# power.net
KiCad netlist of a schematic drawn in Altium Designer
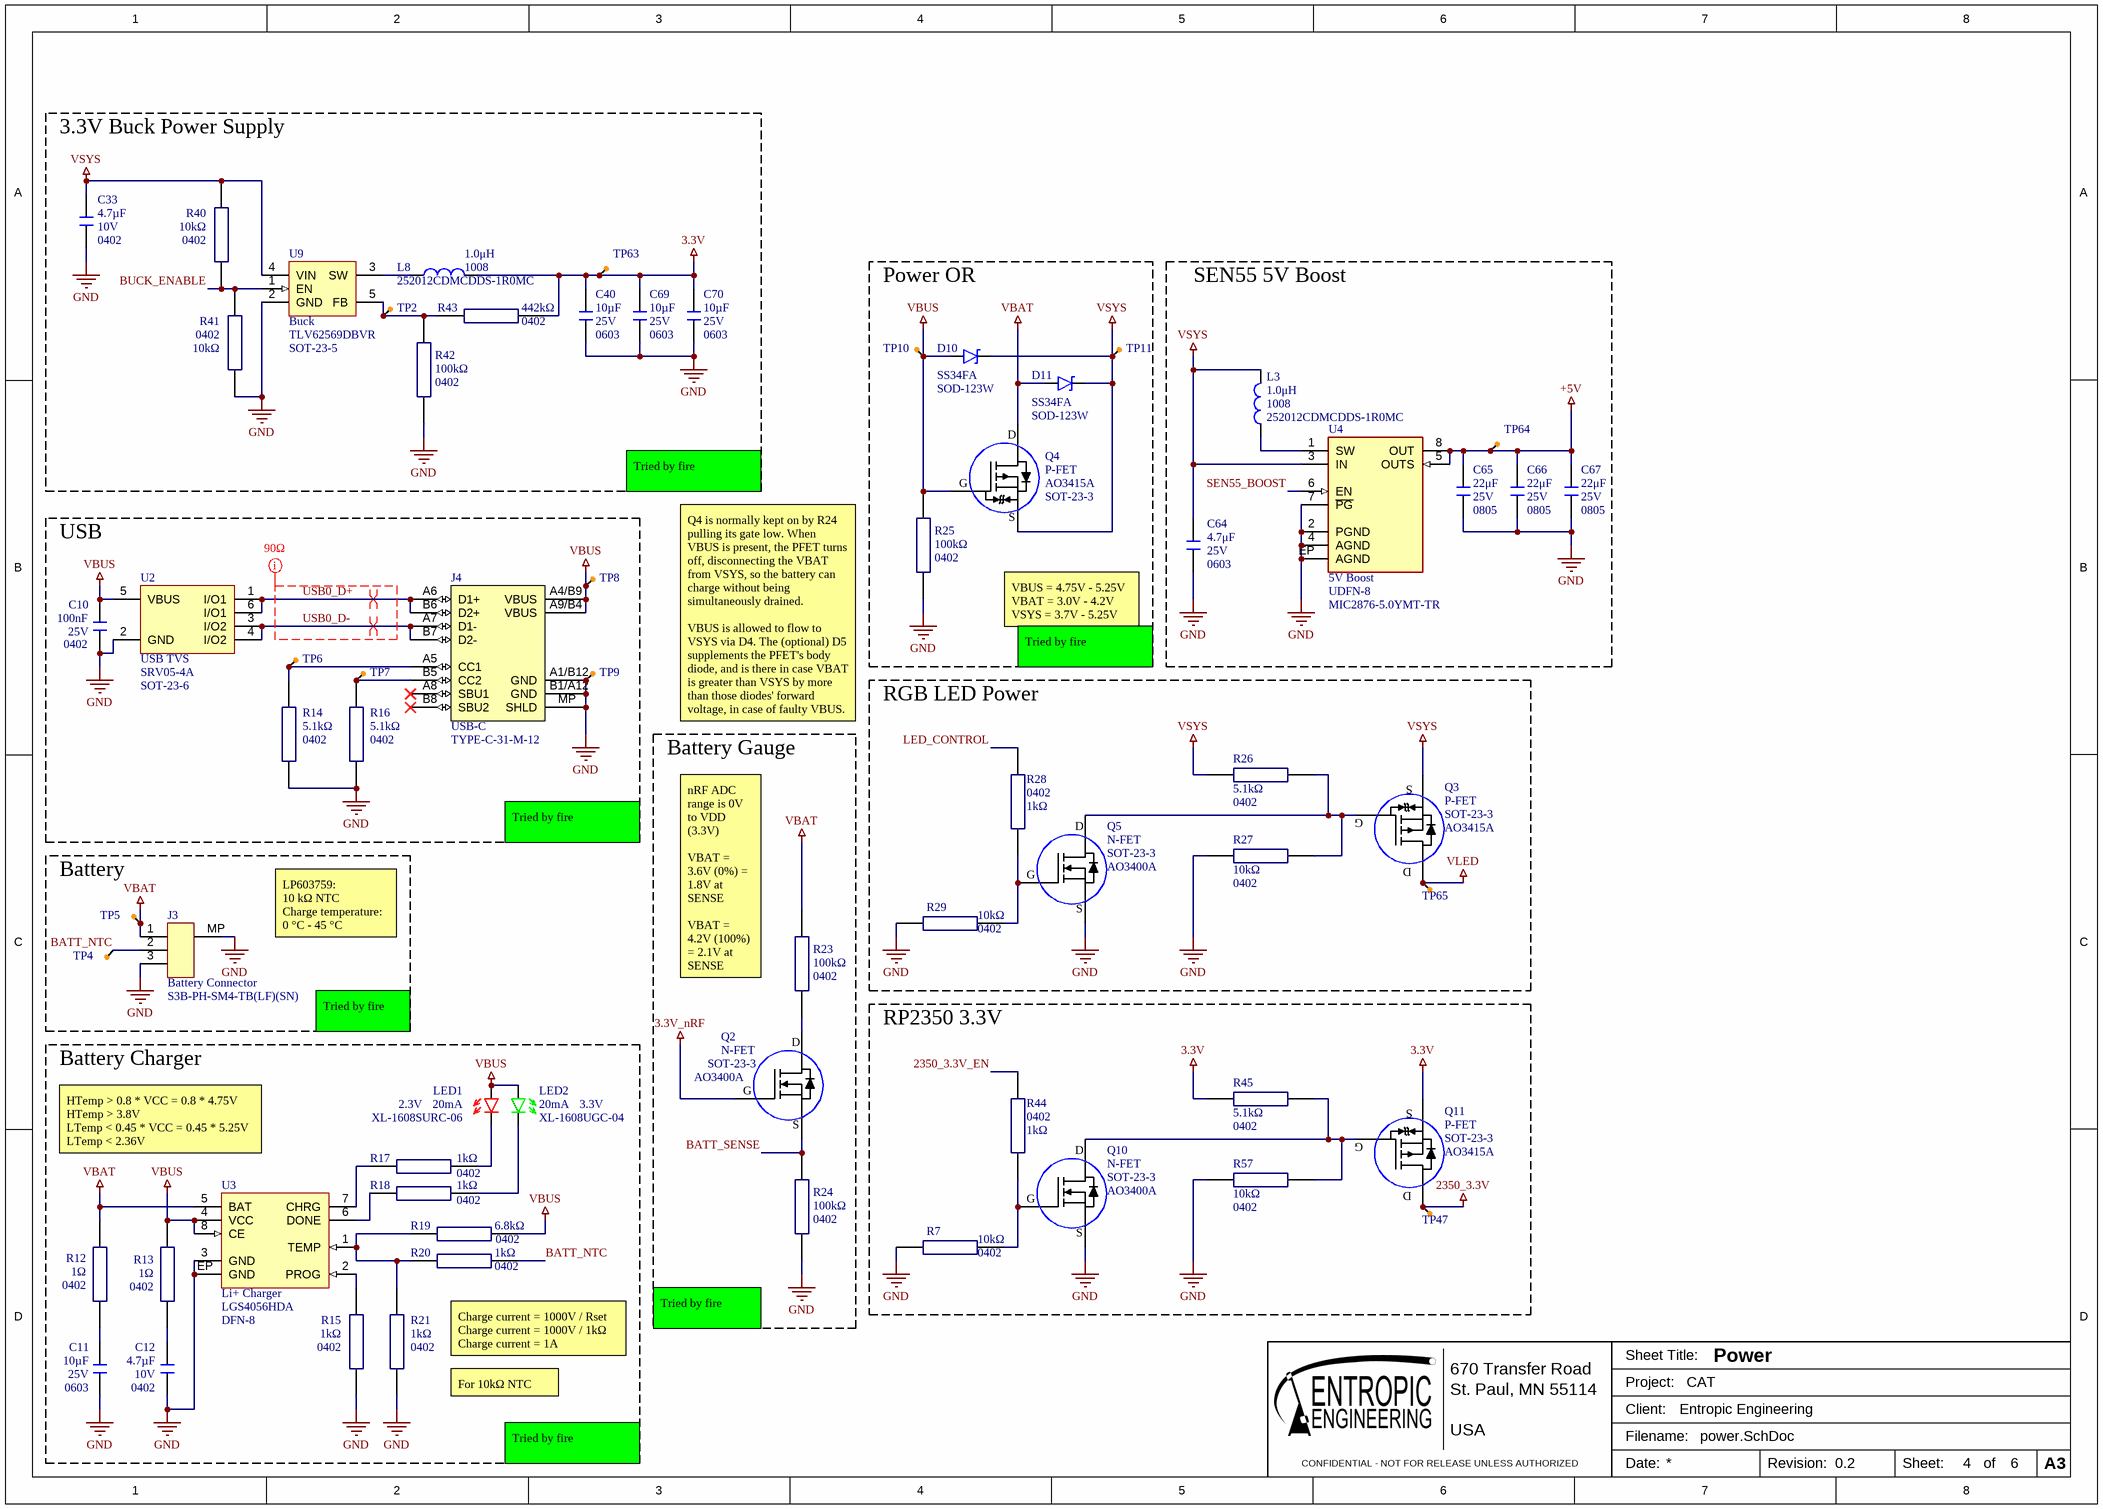
[diagram p0: power.SchDoc]

(export (version "E")
  (design (tool "Eeschema 10.0.6"))
  (components
    (comp (ref "C10")
      (value "GRM155R71E104KE14D")
      (footprint "0402_capacitor")
      (description "100 nF, 25 V, X7R, 0402 Chip capacitor")
      (fields
        (field (name "MANUFACTURER") "Murata")
        (field (name "TOLERANCE") "10%")
        (field (name "CASE CODE (IMPERIAL)") "0402")
        (field (name "VOLTAGE") "25V")
        (field (name "CAPACITANCE") "100nF")
      )
      (libsource (lib "cat") (part "GRM155R71E104KE14D"))
    )
    (comp (ref "C11")
      (value "10µF")
      (footprint "0603_capacitor")
      (description "10 µF, 25 V, X5R, 0603 Chip capacitor")
      (fields
        (field (name "MANUFACTURER") "Samsung")
        (field (name "CASE/PACKAGE") "0603")
        (field (name "TOLERANCE") "20%")
        (field (name "VOLTAGE RATING") "25V")
      )
      (libsource (lib "cat") (part "CL10A106MA8NRNC"))
    )
    (comp (ref "C12")
      (value "4.7µF")
      (footprint "0402_capacitor")
      (description "4.7 µF, 10 V, X5R, 0402 Chip capacitor")
      (fields
        (field (name "MANUFACTURER") "Samsung")
        (field (name "MANUFACTURER PART NUMBER") "CL05A475KP5NRNC")
        (field (name "VOLTAGE RATING") "10V")
        (field (name "CASE/PACKAGE") "0402")
      )
      (libsource (lib "cat") (part "CL05A475KP5NRNC"))
    )
    (comp (ref "C33")
      (value "4.7µF")
      (footprint "0402_capacitor")
      (description "4.7 µF, 10 V, X5R, 0402 Chip capacitor")
      (fields
        (field (name "MANUFACTURER") "Samsung")
        (field (name "MANUFACTURER PART NUMBER") "CL05A475KP5NRNC")
        (field (name "VOLTAGE RATING") "10V")
        (field (name "CASE/PACKAGE") "0402")
      )
      (libsource (lib "cat") (part "CL05A475KP5NRNC"))
    )
    (comp (ref "C40")
      (value "10µF")
      (footprint "0603_capacitor")
      (description "10 µF, 25 V, X5R, 0603 Chip capacitor")
      (fields
        (field (name "MANUFACTURER") "Samsung")
        (field (name "CASE/PACKAGE") "0603")
        (field (name "TOLERANCE") "20%")
        (field (name "VOLTAGE RATING") "25V")
      )
      (libsource (lib "cat") (part "CL10A106MA8NRNC"))
    )
    (comp (ref "C64")
      (value "4.7μF")
      (footprint "0603_capacitor")
      (description "4.7 μF, 25 V, X7R, 0603 Chip capacitor")
      (fields
        (field (name "MANUFACTURER") "TDK")
        (field (name "MANUFACTURER PART NUMBER") "C1608X5R1E475K080AC")
        (field (name "CASE/PACKAGE") "0603")
        (field (name "VOLTAGE RATING") "25V")
      )
      (libsource (lib "cat") (part "C1608X5R1E475K080AC"))
    )
    (comp (ref "C65")
      (value "22μF")
      (footprint "0805_capacitor")
      (description "22 μF, 25 V, X5R, 0805 Chip capacitor")
      (fields
        (field (name "MANUFACTURER") "Murata")
        (field (name "MANUFACTURER PART NUMBER") "GRT21BR61E226ME13L")
        (field (name "RATED DC VOLTAGE (URDC)") "25V")
        (field (name "CASE/PACKAGE") "0805")
      )
      (libsource (lib "cat") (part "GRT21BR61E226ME13L"))
    )
    (comp (ref "C66")
      (value "22μF")
      (footprint "0805_capacitor")
      (description "22 μF, 25 V, X5R, 0805 Chip capacitor")
      (fields
        (field (name "MANUFACTURER") "Murata")
        (field (name "MANUFACTURER PART NUMBER") "GRT21BR61E226ME13L")
        (field (name "RATED DC VOLTAGE (URDC)") "25V")
        (field (name "CASE/PACKAGE") "0805")
      )
      (libsource (lib "cat") (part "GRT21BR61E226ME13L"))
    )
    (comp (ref "C67")
      (value "22μF")
      (footprint "0805_capacitor")
      (description "22 μF, 25 V, X5R, 0805 Chip capacitor")
      (fields
        (field (name "MANUFACTURER") "Murata")
        (field (name "MANUFACTURER PART NUMBER") "GRT21BR61E226ME13L")
        (field (name "RATED DC VOLTAGE (URDC)") "25V")
        (field (name "CASE/PACKAGE") "0805")
      )
      (libsource (lib "cat") (part "GRT21BR61E226ME13L"))
    )
    (comp (ref "C69")
      (value "10µF")
      (footprint "0603_capacitor")
      (description "10 µF, 25 V, X5R, 0603 Chip capacitor")
      (fields
        (field (name "MANUFACTURER") "Samsung")
        (field (name "CASE/PACKAGE") "0603")
        (field (name "TOLERANCE") "20%")
        (field (name "VOLTAGE RATING") "25V")
      )
      (libsource (lib "cat") (part "CL10A106MA8NRNC"))
    )
    (comp (ref "C70")
      (value "10µF")
      (footprint "0603_capacitor")
      (description "10 µF, 25 V, X5R, 0603 Chip capacitor")
      (fields
        (field (name "MANUFACTURER") "Samsung")
        (field (name "CASE/PACKAGE") "0603")
        (field (name "TOLERANCE") "20%")
        (field (name "VOLTAGE RATING") "25V")
      )
      (libsource (lib "cat") (part "CL10A106MA8NRNC"))
    )
    (comp (ref "D10")
      (value "SS34FA")
      (footprint "SOD-123")
      (description "40 V, 3 A Schottky Rectifier, SOD-123FA")
      (fields
        (field (name "MANUFACTURER") "ON Semiconductor / Fairchild")
        (field (name "MANUFACTURER PART NUMBER") "SS34FA")
        (field (name "HOUSE_PART_NUMBER") "D-SCHOTTKY-3A-SOD123F-002")
        (field (name "CASE/PACKAGE") "SOD-123W")
      )
      (libsource (lib "cat") (part "SS34FA"))
    )
    (comp (ref "D11")
      (value "SS34FA")
      (footprint "SOD-123")
      (description "40 V, 3 A Schottky Rectifier, SOD-123FA")
      (fields
        (field (name "MANUFACTURER") "ON Semiconductor / Fairchild")
        (field (name "MANUFACTURER PART NUMBER") "SS34FA")
        (field (name "HOUSE_PART_NUMBER") "D-SCHOTTKY-3A-SOD123F-002")
        (field (name "CASE/PACKAGE") "SOD-123W")
      )
      (libsource (lib "cat") (part "SS34FA"))
    )
    (comp (ref "J3")
      (value "Battery Connector")
      (footprint "S3B-PH-SM4-TB")
      (description "3-Pin JST-PH connector, 2mm pitch, right-angle SMD")
      (fields
        (field (name "MANUFACTURER") "JST")
        (field (name "MANUFACTURER PART NUMBER") "S3B-PH-SM4-TB(LF)(SN)")
        (field (name "HOUSE_PART_NUMBER") "S3B-PH-SM4-TB(LF)(SN)")
      )
      (libsource (lib "cat") (part "S3B-PH-SM4-TB(LF)(SN)"))
    )
    (comp (ref "J4")
      (value "USB-C")
      (footprint "USB_C_2.0_M12")
      (description "USB-C 2.0 Female Connector")
      (fields
        (field (name "MANUFACTURER") "Global Connector Technology")
        (field (name "ALTERNATE PART NUMBER") "USB4105-GF-A")
        (field (name "MANUFACTURER PART NUMBER") "TYPE-C-31-M-12")
      )
      (libsource (lib "cat") (part "USB4105-GF-A"))
    )
    (comp (ref "L3")
      (value "1.0μH")
      (footprint "INDC2520X12N")
      (description "1 μH, 4.2 A, 1008 Inductor")
      (fields
        (field (name "MANUFACTURER") "Sumida")
        (field (name "HOUSE_PART_NUMBER") "L-1uH-1008-002")
        (field (name "PACKAGE") "1008")
        (field (name "MANUFACTURER PART NUMBER") "252012CDMCDDS-1R0MC")
      )
      (libsource (lib "") (part "252012CDMCDDS-1R0MC_1"))
    )
    (comp (ref "L8")
      (value "1.0μH")
      (footprint "INDC2520X12N")
      (description "1 μH, 4.2 A, 1008 Inductor")
      (fields
        (field (name "MANUFACTURER") "Sumida")
        (field (name "PACKAGE") "1008")
        (field (name "MANUFACTURER PART NUMBER") "252012CDMCDDS-1R0MC")
        (field (name "HOUSE_PART_NUMBER") "L-1uH-1008-002")
      )
      (libsource (lib "cat") (part "252012CDMCDDS-1R0MC"))
    )
    (comp (ref "LED1")
      (value "XL-1608SURC-06")
      (footprint "0603_DIODE")
      (description "Red LED, 1.9 - 2.3 V, 20 mA, 0603")
      (fields
        (field (name "MANUFACTURER") "XINGLIGHT")
        (field (name "CURRENT") "20mA")
        (field (name "FORWARD VOLTAGE") "2.3V")
        (field (name "MANUFACTURER PART NUMBER") "XL-1608SURC-06")
      )
      (libsource (lib "cat") (part "XL-1608SURC-06"))
    )
    (comp (ref "LED2")
      (value "XL-1608UGC-04")
      (footprint "0603_DIODE")
      (description "Green LED, 2.7 - 3.3 V, 20 mA, 0603")
      (fields
        (field (name "MANUFACTURER") "XINGLIGHT")
        (field (name "CURRENT") "20mA")
        (field (name "FORWARD VOLTAGE") "3.3V")
        (field (name "MANUFACTURER PART NUMBER") "XL-1608UGC-04")
      )
      (libsource (lib "cat") (part "XL-1608UGC-04"))
    )
    (comp (ref "Q2")
      (value "N-FET")
      (footprint "SOT95P280X115-3N")
      (description "N-FET, 30V, 5.7A, SOT-23-3")
      (fields
        (field (name "MANUFACTURER") "Alpha & Omega Semiconductor")
        (field (name "CASE/PACKAGE") "SOT-23-3")
        (field (name "MANUFACTURER PART NUMBER") "AO3400A")
        (field (name "HOUSE_PART_NUMBER") "AO3400A")
      )
      (libsource (lib "cat") (part "AO3400A"))
    )
    (comp (ref "Q3")
      (value "P-FET")
      (footprint "SOT95P280X115-3N")
      (description "P-FET, 30V, 6A, SOT-23-3")
      (fields
        (field (name "MANUFACTURER") "Alpha & Omega Semiconductor")
        (field (name "CASE/PACKAGE") "SOT-23-3")
        (field (name "MANUFACTURER PART NUMBER") "AO3415A")
        (field (name "HOUSE_PART_NUMBER") "AO3415A")
      )
      (libsource (lib "cat") (part "AO3415A"))
    )
    (comp (ref "Q4")
      (value "P-FET")
      (footprint "SOT95P280X115-3N")
      (description "P-FET, 30V, 6A, SOT-23-3")
      (fields
        (field (name "MANUFACTURER") "Alpha & Omega Semiconductor")
        (field (name "CASE/PACKAGE") "SOT-23-3")
        (field (name "MANUFACTURER PART NUMBER") "AO3415A")
        (field (name "HOUSE_PART_NUMBER") "AO3415A")
      )
      (libsource (lib "cat") (part "AO3415A"))
    )
    (comp (ref "Q5")
      (value "N-FET")
      (footprint "SOT95P280X115-3N")
      (description "N-FET, 30V, 5.7A, SOT-23-3")
      (fields
        (field (name "MANUFACTURER") "Alpha & Omega Semiconductor")
        (field (name "CASE/PACKAGE") "SOT-23-3")
        (field (name "MANUFACTURER PART NUMBER") "AO3400A")
        (field (name "HOUSE_PART_NUMBER") "AO3400A")
      )
      (libsource (lib "cat") (part "AO3400A"))
    )
    (comp (ref "Q10")
      (value "N-FET")
      (footprint "SOT95P280X115-3N")
      (description "N-FET, 30V, 5.7A, SOT-23-3")
      (fields
        (field (name "MANUFACTURER") "Alpha & Omega Semiconductor")
        (field (name "CASE/PACKAGE") "SOT-23-3")
        (field (name "MANUFACTURER PART NUMBER") "AO3400A")
        (field (name "HOUSE_PART_NUMBER") "AO3400A")
      )
      (libsource (lib "cat") (part "AO3400A"))
    )
    (comp (ref "Q11")
      (value "P-FET")
      (footprint "SOT95P280X115-3N")
      (description "P-FET, 30V, 6A, SOT-23-3")
      (fields
        (field (name "MANUFACTURER") "Alpha & Omega Semiconductor")
        (field (name "CASE/PACKAGE") "SOT-23-3")
        (field (name "MANUFACTURER PART NUMBER") "AO3415A")
        (field (name "HOUSE_PART_NUMBER") "AO3415A")
      )
      (libsource (lib "cat") (part "AO3415A"))
    )
    (comp (ref "R7")
      (value "10kΩ")
      (footprint "0402_resistor")
      (description "10 kΩ, 0402 Chip resistor")
      (fields
        (field (name "MANUFACTURER") "Yageo")
        (field (name "MANUFACTURER PART NUMBER") "RC0402FR-0710KL")
        (field (name "CASE CODE (IMPERIAL)") "0402")
      )
      (libsource (lib "cat") (part "RC0402FR-0710KL"))
    )
    (comp (ref "R12")
      (value "1Ω")
      (footprint "0402_resistor")
      (description "1 Ω, 0402 Chip resistor")
      (fields
        (field (name "MANUFACTURER") "Uniroyal")
        (field (name "MANUFACTURER PART NUMBER") "0402WGF100KTCE")
        (field (name "CASE/PACKAGE") "0402")
      )
      (libsource (lib "cat") (part "0402WGF100KTCE"))
    )
    (comp (ref "R13")
      (value "1Ω")
      (footprint "0402_resistor")
      (description "1 Ω, 0402 Chip resistor")
      (fields
        (field (name "MANUFACTURER") "Uniroyal")
        (field (name "MANUFACTURER PART NUMBER") "0402WGF100KTCE")
        (field (name "CASE/PACKAGE") "0402")
      )
      (libsource (lib "cat") (part "0402WGF100KTCE"))
    )
    (comp (ref "R14")
      (value "5.1kΩ")
      (footprint "0402_resistor")
      (description "5.1 kΩ, 0402 Chip resistor")
      (fields
        (field (name "MANUFACTURER") "Yageo")
        (field (name "MANUFACTURER PART NUMBER") "RC0402FR-075K1L")
        (field (name "CASE/PACKAGE") "0402")
      )
      (libsource (lib "cat") (part "RC0402FR-075K1L"))
    )
    (comp (ref "R15")
      (value "1kΩ")
      (footprint "0402_resistor")
      (description "1 kΩ, 0402 Chip resistor")
      (fields
        (field (name "MANUFACTURER") "Yageo")
        (field (name "MANUFACTURER PART NUMBER") "RC0402JR-071KL")
        (field (name "CASE/PACKAGE") "0402")
      )
      (libsource (lib "cat") (part "RC0402JR-071KL"))
    )
    (comp (ref "R16")
      (value "5.1kΩ")
      (footprint "0402_resistor")
      (description "5.1 kΩ, 0402 Chip resistor")
      (fields
        (field (name "MANUFACTURER") "Yageo")
        (field (name "MANUFACTURER PART NUMBER") "RC0402FR-075K1L")
        (field (name "CASE/PACKAGE") "0402")
      )
      (libsource (lib "cat") (part "RC0402FR-075K1L"))
    )
    (comp (ref "R17")
      (value "1kΩ")
      (footprint "0402_resistor")
      (description "1 kΩ, 0402 Chip resistor")
      (fields
        (field (name "MANUFACTURER") "Yageo")
        (field (name "MANUFACTURER PART NUMBER") "RC0402JR-071KL")
        (field (name "CASE/PACKAGE") "0402")
      )
      (libsource (lib "cat") (part "RC0402JR-071KL"))
    )
    (comp (ref "R18")
      (value "1kΩ")
      (footprint "0402_resistor")
      (description "1 kΩ, 0402 Chip resistor")
      (fields
        (field (name "MANUFACTURER") "Yageo")
        (field (name "MANUFACTURER PART NUMBER") "RC0402JR-071KL")
        (field (name "CASE/PACKAGE") "0402")
      )
      (libsource (lib "cat") (part "RC0402JR-071KL"))
    )
    (comp (ref "R19")
      (value "6.8kΩ")
      (footprint "0402_resistor")
      (description "6.8 kΩ, 0402 Chip resistor")
      (fields
        (field (name "MANUFACTURER") "Yageo")
        (field (name "MANUFACTURER PART NUMBER") "RC0402FR-076K8L")
        (field (name "CASE/PACKAGE") "0402")
      )
      (libsource (lib "cat") (part "RC0402FR-076K8L"))
    )
    (comp (ref "R20")
      (value "1kΩ")
      (footprint "0402_resistor")
      (description "1 kΩ, 0402 Chip resistor")
      (fields
        (field (name "MANUFACTURER") "Yageo")
        (field (name "MANUFACTURER PART NUMBER") "RC0402JR-071KL")
        (field (name "CASE/PACKAGE") "0402")
      )
      (libsource (lib "cat") (part "RC0402JR-071KL"))
    )
    (comp (ref "R21")
      (value "1kΩ")
      (footprint "0402_resistor")
      (description "1 kΩ, 0402 Chip resistor")
      (fields
        (field (name "MANUFACTURER") "Yageo")
        (field (name "MANUFACTURER PART NUMBER") "RC0402JR-071KL")
        (field (name "CASE/PACKAGE") "0402")
      )
      (libsource (lib "cat") (part "RC0402JR-071KL"))
    )
    (comp (ref "R23")
      (value "100kΩ")
      (footprint "0402_resistor")
      (description "100 kΩ, 0402 Chip resistor")
      (fields
        (field (name "MANUFACTURER") "Yageo")
        (field (name "MANUFACTURER PART NUMBER") "RC0402FR-07100KL")
        (field (name "CASE/PACKAGE") "0402")
      )
      (libsource (lib "cat") (part "RC0402FR-07100KL"))
    )
    (comp (ref "R24")
      (value "100kΩ")
      (footprint "0402_resistor")
      (description "100 kΩ, 0402 Chip resistor")
      (fields
        (field (name "MANUFACTURER") "Yageo")
        (field (name "MANUFACTURER PART NUMBER") "RC0402FR-07100KL")
        (field (name "CASE/PACKAGE") "0402")
      )
      (libsource (lib "cat") (part "RC0402FR-07100KL"))
    )
    (comp (ref "R25")
      (value "100kΩ")
      (footprint "0402_resistor")
      (description "100 kΩ, 0402 Chip resistor")
      (fields
        (field (name "MANUFACTURER") "Yageo")
        (field (name "MANUFACTURER PART NUMBER") "RC0402FR-07100KL")
        (field (name "CASE/PACKAGE") "0402")
      )
      (libsource (lib "cat") (part "RC0402FR-07100KL"))
    )
    (comp (ref "R26")
      (value "5.1kΩ")
      (footprint "0402_resistor")
      (description "5.1 kΩ, 0402 Chip resistor")
      (fields
        (field (name "MANUFACTURER") "Yageo")
        (field (name "MANUFACTURER PART NUMBER") "RC0402FR-075K1L")
        (field (name "CASE/PACKAGE") "0402")
      )
      (libsource (lib "cat") (part "RC0402FR-075K1L"))
    )
    (comp (ref "R27")
      (value "10kΩ")
      (footprint "0402_resistor")
      (description "10 kΩ, 0402 Chip resistor")
      (fields
        (field (name "MANUFACTURER") "Yageo")
        (field (name "MANUFACTURER PART NUMBER") "RC0402FR-0710KL")
        (field (name "CASE CODE (IMPERIAL)") "0402")
      )
      (libsource (lib "cat") (part "RC0402FR-0710KL"))
    )
    (comp (ref "R28")
      (value "1kΩ")
      (footprint "0402_resistor")
      (description "1 kΩ, 0402 Chip resistor")
      (fields
        (field (name "MANUFACTURER") "Yageo")
        (field (name "MANUFACTURER PART NUMBER") "RC0402JR-071KL")
        (field (name "CASE/PACKAGE") "0402")
      )
      (libsource (lib "cat") (part "RC0402JR-071KL"))
    )
    (comp (ref "R29")
      (value "10kΩ")
      (footprint "0402_resistor")
      (description "10 kΩ, 0402 Chip resistor")
      (fields
        (field (name "MANUFACTURER") "Yageo")
        (field (name "MANUFACTURER PART NUMBER") "RC0402FR-0710KL")
        (field (name "CASE CODE (IMPERIAL)") "0402")
      )
      (libsource (lib "cat") (part "RC0402FR-0710KL"))
    )
    (comp (ref "R40")
      (value "10kΩ")
      (footprint "0402_resistor")
      (description "10 kΩ, 0402 Chip resistor")
      (fields
        (field (name "MANUFACTURER") "Yageo")
        (field (name "MANUFACTURER PART NUMBER") "RC0402FR-0710KL")
        (field (name "CASE CODE (IMPERIAL)") "0402")
      )
      (libsource (lib "cat") (part "RC0402FR-0710KL"))
    )
    (comp (ref "R41")
      (value "10kΩ")
      (footprint "0402_resistor")
      (description "10 kΩ, 0402 Chip resistor")
      (fields
        (field (name "MANUFACTURER") "Yageo")
        (field (name "MANUFACTURER PART NUMBER") "RC0402FR-0710KL")
        (field (name "CASE CODE (IMPERIAL)") "0402")
      )
      (libsource (lib "cat") (part "RC0402FR-0710KL"))
    )
    (comp (ref "R42")
      (value "100kΩ")
      (footprint "0402_resistor")
      (description "100 kΩ, 0402 Chip resistor")
      (fields
        (field (name "MANUFACTURER") "Yageo")
        (field (name "MANUFACTURER PART NUMBER") "RC0402FR-07100KL")
        (field (name "CASE/PACKAGE") "0402")
      )
      (libsource (lib "cat") (part "RC0402FR-07100KL"))
    )
    (comp (ref "R43")
      (value "442kΩ")
      (footprint "0402_resistor")
      (description "442 kΩ, 0402 Chip resistor")
      (fields
        (field (name "MANUFACTURER") "Yageo")
        (field (name "MANUFACTURER PART NUMBER") "RC0402FR-07442KL")
        (field (name "CASE/PACKAGE") "0402")
      )
      (libsource (lib "cat") (part "RC0402FR-07442KL"))
    )
    (comp (ref "R44")
      (value "1kΩ")
      (footprint "0402_resistor")
      (description "1 kΩ, 0402 Chip resistor")
      (fields
        (field (name "MANUFACTURER") "Yageo")
        (field (name "MANUFACTURER PART NUMBER") "RC0402JR-071KL")
        (field (name "CASE/PACKAGE") "0402")
      )
      (libsource (lib "cat") (part "RC0402JR-071KL"))
    )
    (comp (ref "R45")
      (value "5.1kΩ")
      (footprint "0402_resistor")
      (description "5.1 kΩ, 0402 Chip resistor")
      (fields
        (field (name "MANUFACTURER") "Yageo")
        (field (name "MANUFACTURER PART NUMBER") "RC0402FR-075K1L")
        (field (name "CASE/PACKAGE") "0402")
      )
      (libsource (lib "cat") (part "RC0402FR-075K1L"))
    )
    (comp (ref "R57")
      (value "10kΩ")
      (footprint "0402_resistor")
      (description "10 kΩ, 0402 Chip resistor")
      (fields
        (field (name "MANUFACTURER") "Yageo")
        (field (name "MANUFACTURER PART NUMBER") "RC0402FR-0710KL")
        (field (name "CASE CODE (IMPERIAL)") "0402")
      )
      (libsource (lib "cat") (part "RC0402FR-0710KL"))
    )
    (comp (ref "TP2")
      (value "test_point-1")
      (footprint "test_point-1")
      (description "Test point")
      (libsource (lib "cat") (part "test_point-1"))
    )
    (comp (ref "TP4")
      (value "test_point-1")
      (footprint "test_point-1")
      (description "Test point")
      (libsource (lib "cat") (part "test_point-1"))
    )
    (comp (ref "TP5")
      (value "VBAT")
      (footprint "test_point-1")
      (description "Test point")
      (libsource (lib "cat") (part "test_point-1"))
    )
    (comp (ref "TP6")
      (value "test_point-1")
      (footprint "test_point-1")
      (description "Test point")
      (libsource (lib "cat") (part "test_point-1"))
    )
    (comp (ref "TP7")
      (value "test_point-1")
      (footprint "test_point-1")
      (description "Test point")
      (libsource (lib "cat") (part "test_point-1"))
    )
    (comp (ref "TP8")
      (value "VBUS")
      (footprint "test_point-1")
      (description "Test point")
      (libsource (lib "cat") (part "test_point-1"))
    )
    (comp (ref "TP9")
      (value "GND")
      (footprint "test_point-1")
      (description "Test point")
      (libsource (lib "cat") (part "test_point-1"))
    )
    (comp (ref "TP10")
      (value "VBUS")
      (footprint "test_point-1")
      (description "Test point")
      (libsource (lib "cat") (part "test_point-1"))
    )
    (comp (ref "TP11")
      (value "VSYS")
      (footprint "test_point-1")
      (description "Test point")
      (libsource (lib "cat") (part "test_point-1"))
    )
    (comp (ref "TP47")
      (value "VLED")
      (footprint "test_point-1")
      (description "Test point")
      (libsource (lib "cat") (part "test_point-1"))
    )
    (comp (ref "TP63")
      (value "Main 3.3V")
      (footprint "test_point-1")
      (description "Test point")
      (libsource (lib "cat") (part "test_point-1"))
    )
    (comp (ref "TP64")
      (value "Sensors 5V")
      (footprint "test_point-1")
      (description "Test point")
      (libsource (lib "cat") (part "test_point-1"))
    )
    (comp (ref "TP65")
      (value "VLED")
      (footprint "test_point-1")
      (description "Test point")
      (libsource (lib "cat") (part "test_point-1"))
    )
    (comp (ref "U2")
      (value "USB TVS")
      (footprint "SOT95P280X110-6N")
      (description "TVS DIODE ARRAY SOT23-6")
      (fields
        (field (name "MANUFACTURER") "SMC Diodes")
        (field (name "CASE/PACKAGE") "SOT-23-6")
        (field (name "MANUFACTURER PART NUMBER") "SRV05-4A")
        (field (name "HOUSE_PART_NUMBER") "SRV05-4A")
      )
      (libsource (lib "cat") (part "SRV05-4A"))
    )
    (comp (ref "U3")
      (value "Li+ Charger")
      (footprint "SON50P200X80_HS-9N")
      (description "Battery Charger, DFN-8(2x2)")
      (fields
        (field (name "MANUFACTURER PART NUMBER") "LGS4056HDA")
        (field (name "PACKAGE") "DFN-8")
        (field (name "HOUSE_PART_NUMBER") "LGS4056HDA")
      )
      (libsource (lib "cat") (part "LGS4056H"))
    )
    (comp (ref "U4")
      (value "5V Boost")
      (footprint "SON50P200X50_HS-9N")
      (description "5V Synchronous Boost, UDFN-8")
      (fields
        (field (name "MANUFACTURER") "Microchip")
        (field (name "CASE/PACKAGE") "UDFN-8")
        (field (name "MANUFACTURER PART NUMBER") "MIC2876-5.0YMT-TR")
      )
      (libsource (lib "cat") (part "MIC2876-5.0YMT-TR"))
    )
    (comp (ref "U9")
      (value "Buck")
      (footprint "SOT95P280X115-5N")
      (description "Buck converter, 2.5-5.5 Vin, 0.6 - 5.5 Vout, 2A, SOT-23-5")
      (fields
        (field (name "MANUFACTURER") "Texas Instruments")
        (field (name "MANUFACTURER PART NUMBER") "TLV62569DBVR")
        (field (name "CASE/PACKAGE") "SOT-23-5")
        (field (name "HOUSE_PART_NUMBER") "TLV62569DBVR")
      )
      (libsource (lib "cat") (part "TLV62569DBVR"))
    )
  )
  (nets
    (net (code "1") (name "+5V") (class "Default")
      (node (ref "C65") (pin "2") (pinfunction "2_2") (pintype "passive"))
      (node (ref "C66") (pin "2") (pinfunction "2_2") (pintype "passive"))
      (node (ref "C67") (pin "2") (pinfunction "2_2") (pintype "passive"))
      (node (ref "TP64") (pin "1") (pinfunction "1_1") (pintype "passive"))
      (node (ref "U4") (pin "5") (pinfunction "OUTS_5") (pintype "input"))
      (node (ref "U4") (pin "8") (pinfunction "OUT_8") (pintype "power_in"))
    )
    (net (code "2") (name "/2350_3.3V_EN") (class "Default")
      (node (ref "R44") (pin "1") (pinfunction "1_1") (pintype "passive"))
    )
    (net (code "3") (name "/BATT_NTC") (class "Default")
      (node (ref "J3") (pin "2") (pintype "passive"))
      (node (ref "R20") (pin "1") (pinfunction "1_1") (pintype "passive"))
      (node (ref "TP4") (pin "1") (pinfunction "1_1") (pintype "passive"))
    )
    (net (code "4") (name "/BATT_SENSE") (class "Default")
      (node (ref "Q2") (pin "2") (pinfunction "S_2") (pintype "passive"))
      (node (ref "R24") (pin "2") (pinfunction "2_2") (pintype "passive"))
    )
    (net (code "5") (name "/BUCK_ENABLE") (class "Default")
      (node (ref "R40") (pin "1") (pinfunction "1_1") (pintype "passive"))
      (node (ref "R41") (pin "2") (pinfunction "2_2") (pintype "passive"))
      (node (ref "U9") (pin "1") (pinfunction "EN_1") (pintype "input"))
    )
    (net (code "6") (name "/LED_CONTROL") (class "Default")
      (node (ref "R28") (pin "1") (pinfunction "1_1") (pintype "passive"))
    )
    (net (code "7") (name "/SEN55_BOOST") (class "Default")
      (node (ref "U4") (pin "6") (pinfunction "EN_6") (pintype "input"))
    )
    (net (code "8") (name "/USB0_D+") (class "Default")
      (node (ref "J4") (pin "A6") (pinfunction "D1+_A6") (pintype "bidirectional"))
      (node (ref "J4") (pin "B6") (pinfunction "D2+_B6") (pintype "bidirectional"))
      (node (ref "U2") (pin "1") (pinfunction "I/O1_1") (pintype "passive"))
      (node (ref "U2") (pin "6") (pinfunction "I/O1_6") (pintype "passive"))
    )
    (net (code "9") (name "/USB0_D-") (class "Default")
      (node (ref "J4") (pin "A7") (pinfunction "D1-_A7") (pintype "bidirectional"))
      (node (ref "J4") (pin "B7") (pinfunction "D2-_B7") (pintype "bidirectional"))
      (node (ref "U2") (pin "3") (pinfunction "I/O2_3") (pintype "passive"))
      (node (ref "U2") (pin "4") (pinfunction "I/O2_4") (pintype "passive"))
    )
    (net (code "10") (name "3.3V") (class "Default")
      (node (ref "C40") (pin "2") (pinfunction "2_2") (pintype "passive"))
      (node (ref "C69") (pin "2") (pinfunction "2_2") (pintype "passive"))
      (node (ref "C70") (pin "2") (pinfunction "2_2") (pintype "passive"))
      (node (ref "L8") (pin "2") (pinfunction "2_2") (pintype "passive"))
      (node (ref "Q11") (pin "2") (pinfunction "S_2") (pintype "power_in"))
      (node (ref "R43") (pin "2") (pinfunction "2_2") (pintype "passive"))
      (node (ref "R45") (pin "2") (pinfunction "2_2") (pintype "passive"))
      (node (ref "TP63") (pin "1") (pinfunction "1_1") (pintype "passive"))
    )
    (net (code "11") (name "3.3V_nRF") (class "Default")
      (node (ref "Q2") (pin "1") (pinfunction "G_1") (pintype "passive"))
    )
    (net (code "12") (name "2350_3.3V") (class "Default")
      (node (ref "Q11") (pin "3") (pinfunction "D_3") (pintype "power_in"))
      (node (ref "TP47") (pin "1") (pinfunction "1_1") (pintype "passive"))
    )
    (net (code "13") (name "GND") (class "Default")
      (node (ref "C10") (pin "1") (pinfunction "1_1") (pintype "passive"))
      (node (ref "C11") (pin "1") (pinfunction "1_1") (pintype "passive"))
      (node (ref "C12") (pin "1") (pinfunction "1_1") (pintype "passive"))
      (node (ref "C33") (pin "1") (pinfunction "1_1") (pintype "passive"))
      (node (ref "C40") (pin "1") (pinfunction "1_1") (pintype "passive"))
      (node (ref "C64") (pin "1") (pinfunction "1_1") (pintype "passive"))
      (node (ref "C65") (pin "1") (pinfunction "1_1") (pintype "passive"))
      (node (ref "C66") (pin "1") (pinfunction "1_1") (pintype "passive"))
      (node (ref "C67") (pin "1") (pinfunction "1_1") (pintype "passive"))
      (node (ref "C69") (pin "1") (pinfunction "1_1") (pintype "passive"))
      (node (ref "C70") (pin "1") (pinfunction "1_1") (pintype "passive"))
      (node (ref "J3") (pin "3") (pintype "passive"))
      (node (ref "J3") (pin "MP") (pintype "passive"))
      (node (ref "J4") (pin "A1/B12") (pinfunction "GND_A1/B12") (pintype "power_in"))
      (node (ref "J4") (pin "B1/A12") (pinfunction "GND_B1/A12") (pintype "power_in"))
      (node (ref "J4") (pin "MP") (pinfunction "SHLD_MP") (pintype "passive"))
      (node (ref "Q10") (pin "2") (pinfunction "S_2") (pintype "passive"))
      (node (ref "Q5") (pin "2") (pinfunction "S_2") (pintype "passive"))
      (node (ref "R14") (pin "1") (pinfunction "1_1") (pintype "passive"))
      (node (ref "R15") (pin "1") (pinfunction "1_1") (pintype "passive"))
      (node (ref "R16") (pin "1") (pinfunction "1_1") (pintype "passive"))
      (node (ref "R21") (pin "1") (pinfunction "1_1") (pintype "passive"))
      (node (ref "R24") (pin "1") (pinfunction "1_1") (pintype "passive"))
      (node (ref "R25") (pin "1") (pinfunction "1_1") (pintype "passive"))
      (node (ref "R27") (pin "2") (pinfunction "2_2") (pintype "passive"))
      (node (ref "R29") (pin "2") (pinfunction "2_2") (pintype "passive"))
      (node (ref "R41") (pin "1") (pinfunction "1_1") (pintype "passive"))
      (node (ref "R42") (pin "1") (pinfunction "1_1") (pintype "passive"))
      (node (ref "R57") (pin "2") (pinfunction "2_2") (pintype "passive"))
      (node (ref "R7") (pin "2") (pinfunction "2_2") (pintype "passive"))
      (node (ref "TP9") (pin "1") (pinfunction "1_1") (pintype "passive"))
      (node (ref "U2") (pin "2") (pinfunction "GND_2") (pintype "passive"))
      (node (ref "U3") (pin "3") (pinfunction "GND_3") (pintype "power_in"))
      (node (ref "U3") (pin "EP") (pinfunction "GND_EP") (pintype "power_in"))
      (node (ref "U4") (pin "2") (pinfunction "PGND_2") (pintype "power_in"))
      (node (ref "U4") (pin "4") (pinfunction "AGND_4") (pintype "power_in"))
      (node (ref "U4") (pin "7") (pinfunction "~{PG}_7") (pintype "open_collector"))
      (node (ref "U4") (pin "EP") (pinfunction "AGND_EP") (pintype "power_in"))
      (node (ref "U9") (pin "2") (pinfunction "GND_2") (pintype "power_in"))
    )
    (net (code "14") (name "Net-(C11-Pad2)") (class "Default")
      (node (ref "C11") (pin "2") (pinfunction "2_2") (pintype "passive"))
      (node (ref "R12") (pin "1") (pinfunction "1_1") (pintype "passive"))
    )
    (net (code "15") (name "Net-(C12-Pad2)") (class "Default")
      (node (ref "C12") (pin "2") (pinfunction "2_2") (pintype "passive"))
      (node (ref "R13") (pin "1") (pinfunction "1_1") (pintype "passive"))
    )
    (net (code "16") (name "Net-(J4-CC1)") (class "Default")
      (node (ref "J4") (pin "A5") (pinfunction "CC1_A5") (pintype "bidirectional"))
      (node (ref "R14") (pin "2") (pinfunction "2_2") (pintype "passive"))
      (node (ref "TP6") (pin "1") (pinfunction "1_1") (pintype "passive"))
    )
    (net (code "17") (name "Net-(J4-CC2)") (class "Default")
      (node (ref "J4") (pin "B5") (pinfunction "CC2_B5") (pintype "bidirectional"))
      (node (ref "R16") (pin "2") (pinfunction "2_2") (pintype "passive"))
      (node (ref "TP7") (pin "1") (pinfunction "1_1") (pintype "passive"))
    )
    (net (code "18") (name "Net-(LED1-Pad1)") (class "Default")
      (node (ref "LED1") (pin "1") (pinfunction "1_1") (pintype "passive"))
      (node (ref "R17") (pin "1") (pinfunction "1_1") (pintype "passive"))
    )
    (net (code "19") (name "Net-(LED2-Pad1)") (class "Default")
      (node (ref "LED2") (pin "1") (pinfunction "1_1") (pintype "passive"))
      (node (ref "R18") (pin "1") (pinfunction "1_1") (pintype "passive"))
    )
    (net (code "20") (name "Net-(Q2-D)") (class "Default")
      (node (ref "Q2") (pin "3") (pinfunction "D_3") (pintype "passive"))
      (node (ref "R23") (pin "1") (pinfunction "1_1") (pintype "passive"))
    )
    (net (code "21") (name "Net-(Q3-G)") (class "Default")
      (node (ref "Q3") (pin "1") (pinfunction "G_1") (pintype "power_in"))
      (node (ref "Q5") (pin "3") (pinfunction "D_3") (pintype "passive"))
      (node (ref "R26") (pin "1") (pinfunction "1_1") (pintype "passive"))
      (node (ref "R27") (pin "1") (pinfunction "1_1") (pintype "passive"))
    )
    (net (code "22") (name "Net-(Q5-G)") (class "Default")
      (node (ref "Q5") (pin "1") (pinfunction "G_1") (pintype "passive"))
      (node (ref "R28") (pin "2") (pinfunction "2_2") (pintype "passive"))
      (node (ref "R29") (pin "1") (pinfunction "1_1") (pintype "passive"))
    )
    (net (code "23") (name "Net-(Q10-D)") (class "Default")
      (node (ref "Q10") (pin "3") (pinfunction "D_3") (pintype "passive"))
      (node (ref "Q11") (pin "1") (pinfunction "G_1") (pintype "power_in"))
      (node (ref "R45") (pin "1") (pinfunction "1_1") (pintype "passive"))
      (node (ref "R57") (pin "1") (pinfunction "1_1") (pintype "passive"))
    )
    (net (code "24") (name "Net-(Q10-G)") (class "Default")
      (node (ref "Q10") (pin "1") (pinfunction "G_1") (pintype "passive"))
      (node (ref "R44") (pin "2") (pinfunction "2_2") (pintype "passive"))
      (node (ref "R7") (pin "1") (pinfunction "1_1") (pintype "passive"))
    )
    (net (code "25") (name "Net-(U3-CHRG)") (class "Default")
      (node (ref "R17") (pin "2") (pinfunction "2_2") (pintype "passive"))
      (node (ref "U3") (pin "7") (pinfunction "CHRG_7") (pintype "open_collector"))
    )
    (net (code "26") (name "Net-(U3-DONE)") (class "Default")
      (node (ref "R18") (pin "2") (pinfunction "2_2") (pintype "passive"))
      (node (ref "U3") (pin "6") (pinfunction "DONE_6") (pintype "open_collector"))
    )
    (net (code "27") (name "Net-(U3-PROG)") (class "Default")
      (node (ref "R15") (pin "2") (pinfunction "2_2") (pintype "passive"))
      (node (ref "U3") (pin "2") (pinfunction "PROG_2") (pintype "input"))
    )
    (net (code "28") (name "Net-(U3-TEMP)") (class "Default")
      (node (ref "R19") (pin "2") (pinfunction "2_2") (pintype "passive"))
      (node (ref "R20") (pin "2") (pinfunction "2_2") (pintype "passive"))
      (node (ref "R21") (pin "2") (pinfunction "2_2") (pintype "passive"))
      (node (ref "U3") (pin "1") (pinfunction "TEMP_1") (pintype "input"))
    )
    (net (code "29") (name "Net-(U4-SW)") (class "Default")
      (node (ref "L3") (pin "2") (pinfunction "2_2") (pintype "passive"))
      (node (ref "U4") (pin "1") (pinfunction "SW_1") (pintype "power_in"))
    )
    (net (code "30") (name "Net-(U9-FB)") (class "Default")
      (node (ref "R42") (pin "2") (pinfunction "2_2") (pintype "passive"))
      (node (ref "R43") (pin "1") (pinfunction "1_1") (pintype "passive"))
      (node (ref "TP2") (pin "1") (pinfunction "1_1") (pintype "passive"))
      (node (ref "U9") (pin "5") (pinfunction "FB_5") (pintype "power_in"))
    )
    (net (code "31") (name "Net-(U9-SW)") (class "Default")
      (node (ref "L8") (pin "1") (pinfunction "1_1") (pintype "passive"))
      (node (ref "U9") (pin "3") (pinfunction "SW_3") (pintype "power_in"))
    )
    (net (code "32") (name "VBAT") (class "Default")
      (node (ref "D11") (pin "A") (pinfunction "A_A") (pintype "passive"))
      (node (ref "J3") (pin "1") (pintype "passive"))
      (node (ref "Q4") (pin "3") (pinfunction "D_3") (pintype "power_in"))
      (node (ref "R12") (pin "2") (pinfunction "2_2") (pintype "passive"))
      (node (ref "R23") (pin "2") (pinfunction "2_2") (pintype "passive"))
      (node (ref "TP5") (pin "1") (pinfunction "1_1") (pintype "passive"))
      (node (ref "U3") (pin "5") (pinfunction "BAT_5") (pintype "power_in"))
    )
    (net (code "33") (name "VBUS") (class "Default")
      (node (ref "C10") (pin "2") (pinfunction "2_2") (pintype "passive"))
      (node (ref "D10") (pin "A") (pinfunction "A_A") (pintype "passive"))
      (node (ref "J4") (pin "A4/B9") (pinfunction "VBUS_A4/B9") (pintype "power_in"))
      (node (ref "J4") (pin "A9/B4") (pinfunction "VBUS_A9/B4") (pintype "power_in"))
      (node (ref "LED1") (pin "2") (pinfunction "2_2") (pintype "passive"))
      (node (ref "LED2") (pin "2") (pinfunction "2_2") (pintype "passive"))
      (node (ref "Q4") (pin "1") (pinfunction "G_1") (pintype "power_in"))
      (node (ref "R13") (pin "2") (pinfunction "2_2") (pintype "passive"))
      (node (ref "R19") (pin "1") (pinfunction "1_1") (pintype "passive"))
      (node (ref "R25") (pin "2") (pinfunction "2_2") (pintype "passive"))
      (node (ref "TP10") (pin "1") (pinfunction "1_1") (pintype "passive"))
      (node (ref "TP8") (pin "1") (pinfunction "1_1") (pintype "passive"))
      (node (ref "U2") (pin "5") (pinfunction "VBUS_5") (pintype "passive"))
      (node (ref "U3") (pin "4") (pinfunction "VCC_4") (pintype "power_in"))
      (node (ref "U3") (pin "8") (pinfunction "CE_8") (pintype "input"))
    )
    (net (code "34") (name "VLED") (class "Default")
      (node (ref "Q3") (pin "3") (pinfunction "D_3") (pintype "power_in"))
      (node (ref "TP65") (pin "1") (pinfunction "1_1") (pintype "passive"))
    )
    (net (code "35") (name "VSYS") (class "Default")
      (node (ref "C33") (pin "2") (pinfunction "2_2") (pintype "passive"))
      (node (ref "C64") (pin "2") (pinfunction "2_2") (pintype "passive"))
      (node (ref "D10") (pin "K") (pinfunction "K_K") (pintype "passive"))
      (node (ref "D11") (pin "K") (pinfunction "K_K") (pintype "passive"))
      (node (ref "L3") (pin "1") (pinfunction "1_1") (pintype "passive"))
      (node (ref "Q3") (pin "2") (pinfunction "S_2") (pintype "power_in"))
      (node (ref "Q4") (pin "2") (pinfunction "S_2") (pintype "power_in"))
      (node (ref "R26") (pin "2") (pinfunction "2_2") (pintype "passive"))
      (node (ref "R40") (pin "2") (pinfunction "2_2") (pintype "passive"))
      (node (ref "TP11") (pin "1") (pinfunction "1_1") (pintype "passive"))
      (node (ref "U4") (pin "3") (pinfunction "IN_3") (pintype "power_in"))
      (node (ref "U9") (pin "4") (pinfunction "VIN_4") (pintype "power_in"))
    )
    (net (code "36") (name "unconnected-(J4-SBU1-PadA8)") (class "Default")
      (node (ref "J4") (pin "A8") (pinfunction "SBU1_A8") (pintype "bidirectional+no_connect"))
    )
    (net (code "37") (name "unconnected-(J4-SBU2-PadB8)") (class "Default")
      (node (ref "J4") (pin "B8") (pinfunction "SBU2_B8") (pintype "bidirectional+no_connect"))
    )
  )
)
